# Open_Sesame_circuitboard.net
KiCad netlist of a schematic drawn in EAGLE
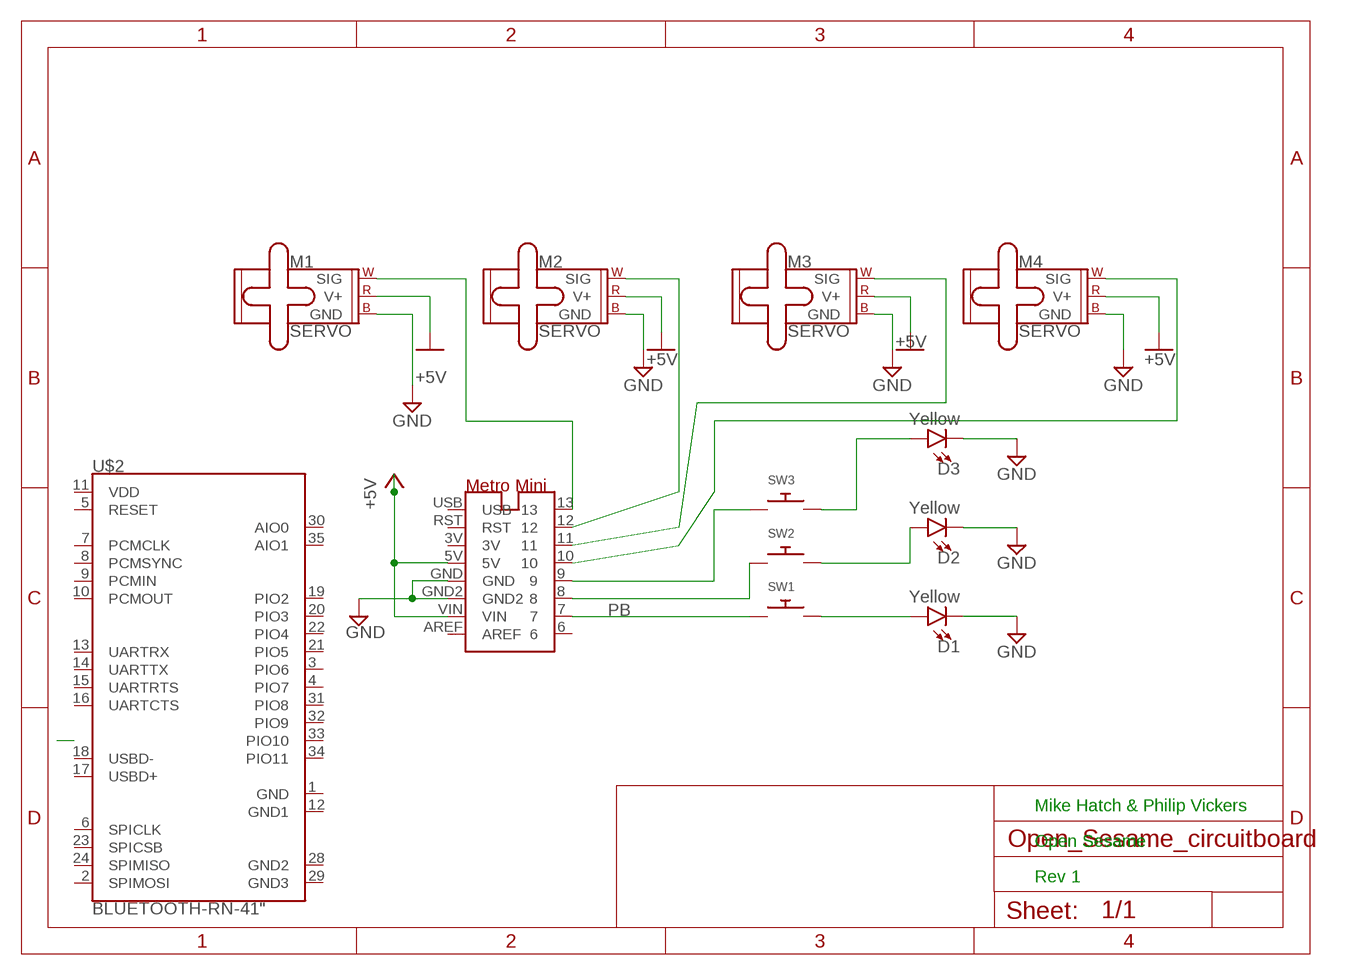
[diagram p0: schematic, sheet 1]

(export (version "E")
  (design (tool "Eeschema 10.0.6"))
  (components
    (comp (ref "D1")
      (value "Yellow")
      (footprint "eagle-import:LED-0603")
      (libsource (lib "eagle-import") (part "LED-YELLOW0603"))
    )
    (comp (ref "D2")
      (value "Yellow")
      (footprint "eagle-import:LED-0603")
      (libsource (lib "eagle-import") (part "LED-YELLOW0603"))
    )
    (comp (ref "D3")
      (value "Yellow")
      (footprint "eagle-import:LED-0603")
      (libsource (lib "eagle-import") (part "LED-YELLOW0603"))
    )
    (comp (ref "M1")
      (value "SERVO")
      (footprint "eagle-import:1X03")
      (libsource (lib "eagle-import") (part "SERVO"))
    )
    (comp (ref "M2")
      (value "SERVO")
      (footprint "eagle-import:1X03")
      (libsource (lib "eagle-import") (part "SERVO"))
    )
    (comp (ref "M3")
      (value "SERVO")
      (footprint "eagle-import:1X03")
      (libsource (lib "eagle-import") (part "SERVO"))
    )
    (comp (ref "M4")
      (value "SERVO")
      (footprint "eagle-import:1X03")
      (libsource (lib "eagle-import") (part "SERVO"))
    )
    (comp (ref "SW1")
      (value "SWITCH_PUSHBUTTONC&K_KSS")
      (footprint "eagle-import:BTN_CK_KSS")
      (libsource (lib "eagle-import") (part "SWITCH_PUSHBUTTONC&K_KSS"))
    )
    (comp (ref "SW2")
      (value "SWITCH_PUSHBUTTONC&K_KSS")
      (footprint "eagle-import:BTN_CK_KSS")
      (libsource (lib "eagle-import") (part "SWITCH_PUSHBUTTONC&K_KSS"))
    )
    (comp (ref "SW3")
      (value "SWITCH_PUSHBUTTONC&K_KSS")
      (footprint "eagle-import:BTN_CK_KSS")
      (libsource (lib "eagle-import") (part "SWITCH_PUSHBUTTONC&K_KSS"))
    )
    (comp (ref "U$1")
      (value "VTC_LIB_METROMINISHIELD")
      (footprint "eagle-import:VTC_LIB_METROMINISHEILD")
      (libsource (lib "eagle-import") (part "VTC_LIB_METROMINISHIELD"))
    )
    (comp (ref "U$2")
      (value "BLUETOOTH-RN-41\"")
      (footprint "eagle-import:RN41")
      (libsource (lib "eagle-import") (part "BLUETOOTH-RN-41{dblquote}"))
    )
  )
  (nets
    (net (code "1") (name "+5V") (class "Default")
      (node (ref "M1") (pin "2") (pinfunction "V+_2") (pintype "bidirectional"))
      (node (ref "M2") (pin "2") (pinfunction "V+_2") (pintype "bidirectional"))
      (node (ref "M3") (pin "2") (pinfunction "V+_2") (pintype "bidirectional"))
      (node (ref "M4") (pin "2") (pinfunction "V+_2") (pintype "bidirectional"))
      (node (ref "U$1") (pin "5V") (pinfunction "5V_5V") (pintype "bidirectional"))
      (node (ref "U$1") (pin "VIN") (pinfunction "VIN_VIN") (pintype "bidirectional"))
    )
    (net (code "2") (name "/PB") (class "Default")
      (node (ref "SW1") (pin "P$1") (pinfunction "P$1_P$1") (pintype "passive"))
      (node (ref "U$1") (pin "7") (pinfunction "7_7") (pintype "bidirectional"))
    )
    (net (code "3") (name "GND") (class "Default")
      (node (ref "D1") (pin "C") (pinfunction "C_C") (pintype "passive"))
      (node (ref "D2") (pin "C") (pinfunction "C_C") (pintype "passive"))
      (node (ref "D3") (pin "C") (pinfunction "C_C") (pintype "passive"))
      (node (ref "M1") (pin "3") (pinfunction "GND_3") (pintype "bidirectional"))
      (node (ref "M2") (pin "3") (pinfunction "GND_3") (pintype "bidirectional"))
      (node (ref "M3") (pin "3") (pinfunction "GND_3") (pintype "bidirectional"))
      (node (ref "M4") (pin "3") (pinfunction "GND_3") (pintype "bidirectional"))
      (node (ref "U$1") (pin "GND") (pinfunction "GND_GND") (pintype "bidirectional"))
      (node (ref "U$1") (pin "GND2") (pinfunction "GND2_GND2") (pintype "bidirectional"))
    )
    (net (code "4") (name "Net-(D1-PadA)") (class "Default")
      (node (ref "D1") (pin "A") (pinfunction "A_A") (pintype "passive"))
      (node (ref "SW1") (pin "P$2") (pinfunction "P$2_P$2") (pintype "passive"))
    )
    (net (code "5") (name "Net-(D2-PadA)") (class "Default")
      (node (ref "D2") (pin "A") (pinfunction "A_A") (pintype "passive"))
      (node (ref "SW2") (pin "P$2") (pinfunction "P$2_P$2") (pintype "passive"))
    )
    (net (code "6") (name "Net-(D3-PadA)") (class "Default")
      (node (ref "D3") (pin "A") (pinfunction "A_A") (pintype "passive"))
      (node (ref "SW3") (pin "P$2") (pinfunction "P$2_P$2") (pintype "passive"))
    )
    (net (code "7") (name "Net-(M1-SIG)") (class "Default")
      (node (ref "M1") (pin "1") (pinfunction "SIG_1") (pintype "bidirectional"))
      (node (ref "U$1") (pin "13") (pinfunction "13_13") (pintype "bidirectional"))
    )
    (net (code "8") (name "Net-(M2-SIG)") (class "Default")
      (node (ref "M2") (pin "1") (pinfunction "SIG_1") (pintype "bidirectional"))
      (node (ref "U$1") (pin "12") (pinfunction "12_12") (pintype "bidirectional"))
    )
    (net (code "9") (name "Net-(M3-SIG)") (class "Default")
      (node (ref "M3") (pin "1") (pinfunction "SIG_1") (pintype "bidirectional"))
      (node (ref "U$1") (pin "11") (pinfunction "11_11") (pintype "bidirectional"))
    )
    (net (code "10") (name "Net-(M4-SIG)") (class "Default")
      (node (ref "M4") (pin "1") (pinfunction "SIG_1") (pintype "bidirectional"))
      (node (ref "U$1") (pin "10") (pinfunction "10_10") (pintype "bidirectional"))
    )
    (net (code "11") (name "Net-(SW2-PadP$1)") (class "Default")
      (node (ref "SW2") (pin "P$1") (pinfunction "P$1_P$1") (pintype "passive"))
      (node (ref "U$1") (pin "8") (pinfunction "8_8") (pintype "bidirectional"))
    )
    (net (code "12") (name "Net-(SW3-PadP$1)") (class "Default")
      (node (ref "SW3") (pin "P$1") (pinfunction "P$1_P$1") (pintype "passive"))
      (node (ref "U$1") (pin "9") (pinfunction "9_9") (pintype "bidirectional"))
    )
    (net (code "13") (name "unconnected-(U$1-Pad3V)") (class "Default")
      (node (ref "U$1") (pin "3V") (pinfunction "3V_3V") (pintype "bidirectional"))
    )
    (net (code "14") (name "unconnected-(U$1-Pad6)") (class "Default")
      (node (ref "U$1") (pin "6") (pinfunction "6_6") (pintype "bidirectional"))
    )
    (net (code "15") (name "unconnected-(U$1-PadAREF)") (class "Default")
      (node (ref "U$1") (pin "AREF") (pinfunction "AREF_AREF") (pintype "bidirectional"))
    )
    (net (code "16") (name "unconnected-(U$1-PadRST)") (class "Default")
      (node (ref "U$1") (pin "RST") (pinfunction "RST_RST") (pintype "bidirectional"))
    )
    (net (code "17") (name "unconnected-(U$1-PadUSB)") (class "Default")
      (node (ref "U$1") (pin "USB") (pinfunction "USB_USB") (pintype "bidirectional"))
    )
    (net (code "18") (name "unconnected-(U$2-AIO0-Pad30)") (class "Default")
      (node (ref "U$2") (pin "30") (pinfunction "AIO0_30") (pintype "bidirectional"))
    )
    (net (code "19") (name "unconnected-(U$2-AIO1-Pad35)") (class "Default")
      (node (ref "U$2") (pin "35") (pinfunction "AIO1_35") (pintype "bidirectional"))
    )
    (net (code "20") (name "unconnected-(U$2-GND-Pad1)") (class "Default")
      (node (ref "U$2") (pin "1") (pinfunction "GND_1") (pintype "bidirectional"))
    )
    (net (code "21") (name "unconnected-(U$2-GND1-Pad12)") (class "Default")
      (node (ref "U$2") (pin "12") (pinfunction "GND1_12") (pintype "bidirectional"))
    )
    (net (code "22") (name "unconnected-(U$2-GND2-Pad28)") (class "Default")
      (node (ref "U$2") (pin "28") (pinfunction "GND2_28") (pintype "bidirectional"))
    )
    (net (code "23") (name "unconnected-(U$2-GND3-Pad29)") (class "Default")
      (node (ref "U$2") (pin "29") (pinfunction "GND3_29") (pintype "bidirectional"))
    )
    (net (code "24") (name "unconnected-(U$2-PCMCLK-Pad7)") (class "Default")
      (node (ref "U$2") (pin "7") (pinfunction "PCMCLK_7") (pintype "bidirectional"))
    )
    (net (code "25") (name "unconnected-(U$2-PCMIN-Pad9)") (class "Default")
      (node (ref "U$2") (pin "9") (pinfunction "PCMIN_9") (pintype "bidirectional"))
    )
    (net (code "26") (name "unconnected-(U$2-PCMOUT-Pad10)") (class "Default")
      (node (ref "U$2") (pin "10") (pinfunction "PCMOUT_10") (pintype "bidirectional"))
    )
    (net (code "27") (name "unconnected-(U$2-PCMSYNC-Pad8)") (class "Default")
      (node (ref "U$2") (pin "8") (pinfunction "PCMSYNC_8") (pintype "bidirectional"))
    )
    (net (code "28") (name "unconnected-(U$2-PIO2-Pad19)") (class "Default")
      (node (ref "U$2") (pin "19") (pinfunction "PIO2_19") (pintype "bidirectional"))
    )
    (net (code "29") (name "unconnected-(U$2-PIO3-Pad20)") (class "Default")
      (node (ref "U$2") (pin "20") (pinfunction "PIO3_20") (pintype "bidirectional"))
    )
    (net (code "30") (name "unconnected-(U$2-PIO4-Pad22)") (class "Default")
      (node (ref "U$2") (pin "22") (pinfunction "PIO4_22") (pintype "bidirectional"))
    )
    (net (code "31") (name "unconnected-(U$2-PIO5-Pad21)") (class "Default")
      (node (ref "U$2") (pin "21") (pinfunction "PIO5_21") (pintype "bidirectional"))
    )
    (net (code "32") (name "unconnected-(U$2-PIO6-Pad3)") (class "Default")
      (node (ref "U$2") (pin "3") (pinfunction "PIO6_3") (pintype "bidirectional"))
    )
    (net (code "33") (name "unconnected-(U$2-PIO7-Pad4)") (class "Default")
      (node (ref "U$2") (pin "4") (pinfunction "PIO7_4") (pintype "bidirectional"))
    )
    (net (code "34") (name "unconnected-(U$2-PIO8-Pad31)") (class "Default")
      (node (ref "U$2") (pin "31") (pinfunction "PIO8_31") (pintype "bidirectional"))
    )
    (net (code "35") (name "unconnected-(U$2-PIO9-Pad32)") (class "Default")
      (node (ref "U$2") (pin "32") (pinfunction "PIO9_32") (pintype "bidirectional"))
    )
    (net (code "36") (name "unconnected-(U$2-PIO10-Pad33)") (class "Default")
      (node (ref "U$2") (pin "33") (pinfunction "PIO10_33") (pintype "bidirectional"))
    )
    (net (code "37") (name "unconnected-(U$2-PIO11-Pad34)") (class "Default")
      (node (ref "U$2") (pin "34") (pinfunction "PIO11_34") (pintype "bidirectional"))
    )
    (net (code "38") (name "unconnected-(U$2-RESET-Pad5)") (class "Default")
      (node (ref "U$2") (pin "5") (pinfunction "RESET_5") (pintype "bidirectional"))
    )
    (net (code "39") (name "unconnected-(U$2-SPICLK-Pad6)") (class "Default")
      (node (ref "U$2") (pin "6") (pinfunction "SPICLK_6") (pintype "bidirectional"))
    )
    (net (code "40") (name "unconnected-(U$2-SPICSB-Pad23)") (class "Default")
      (node (ref "U$2") (pin "23") (pinfunction "SPICSB_23") (pintype "bidirectional"))
    )
    (net (code "41") (name "unconnected-(U$2-SPIMISO-Pad24)") (class "Default")
      (node (ref "U$2") (pin "24") (pinfunction "SPIMISO_24") (pintype "bidirectional"))
    )
    (net (code "42") (name "unconnected-(U$2-SPIMOSI-Pad2)") (class "Default")
      (node (ref "U$2") (pin "2") (pinfunction "SPIMOSI_2") (pintype "bidirectional"))
    )
    (net (code "43") (name "unconnected-(U$2-UARTCTS-Pad16)") (class "Default")
      (node (ref "U$2") (pin "16") (pinfunction "UARTCTS_16") (pintype "bidirectional"))
    )
    (net (code "44") (name "unconnected-(U$2-UARTRTS-Pad15)") (class "Default")
      (node (ref "U$2") (pin "15") (pinfunction "UARTRTS_15") (pintype "bidirectional"))
    )
    (net (code "45") (name "unconnected-(U$2-UARTRX-Pad13)") (class "Default")
      (node (ref "U$2") (pin "13") (pinfunction "UARTRX_13") (pintype "bidirectional"))
    )
    (net (code "46") (name "unconnected-(U$2-UARTTX-Pad14)") (class "Default")
      (node (ref "U$2") (pin "14") (pinfunction "UARTTX_14") (pintype "bidirectional"))
    )
    (net (code "47") (name "unconnected-(U$2-USBD+-Pad17)") (class "Default")
      (node (ref "U$2") (pin "17") (pinfunction "USBD+_17") (pintype "bidirectional"))
    )
    (net (code "48") (name "unconnected-(U$2-USBD--Pad18)") (class "Default")
      (node (ref "U$2") (pin "18") (pinfunction "USBD-_18") (pintype "bidirectional"))
    )
    (net (code "49") (name "unconnected-(U$2-VDD-Pad11)") (class "Default")
      (node (ref "U$2") (pin "11") (pinfunction "VDD_11") (pintype "bidirectional"))
    )
  )
)
